# OUTPUTS.net
KiCad netlist of a schematic drawn in Altium Designer
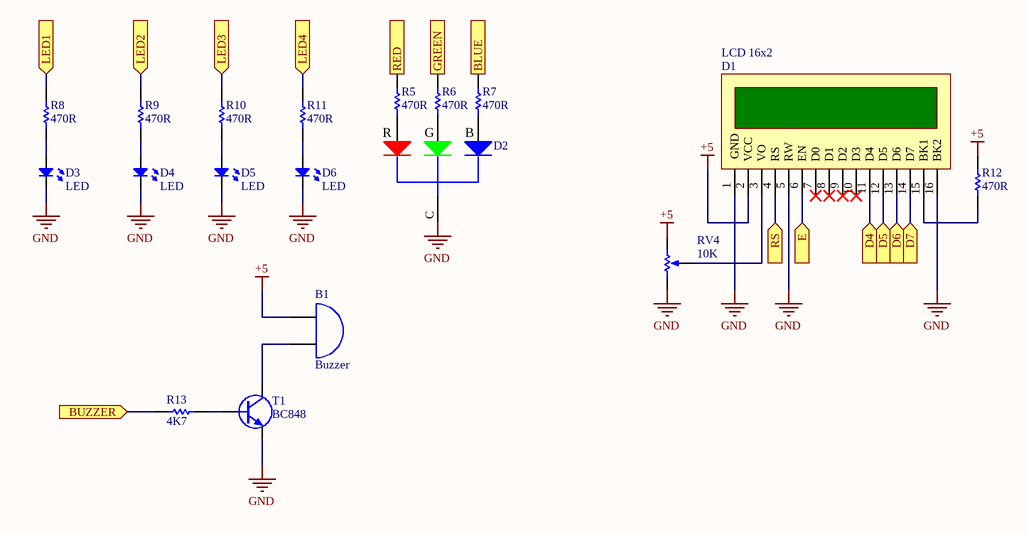
[diagram p0: OUTPUTS.SchDoc]

(export (version "E")
  (design (tool "Eeschema 10.0.6"))
  (components
    (comp (ref "B1")
      (value "Buzzer")
      (footprint "Buzzer")
      (description "Piezoeletric")
      (fields
        (field (name "MANUFACTURER") "Projects Unlimited")
        (field (name "MANUFACTURER PART NUMBER") "AT-1224-TWT-5V-2-R")
      )
      (libsource (lib "Adono_Library2") (part "Buzzer"))
    )
    (comp (ref "D1")
      (value "LCD 16x2")
      (footprint "LCD_16X2")
      (description "Liquid Crystal Display 16x2")
      (fields
        (field (name "MANUFACTURER") "Lumex")
        (field (name "MANUFACTURER PART NUMBER") "LCM-S01602DSR/A")
      )
      (libsource (lib "Adono_Library2") (part "LCD_16x2"))
    )
    (comp (ref "D2")
      (value "Led RGB")
      (footprint "RGB-5mm")
      (description "Led RGB 4 pin Cathode Commom")
      (libsource (lib "Adono_Library2") (part "RGB"))
    )
    (comp (ref "D3")
      (value "LED")
      (footprint "LED_GREEN")
      (description "Light Emissor Diode - 5mm")
      (fields
        (field (name "MANUFACTURER") "Kingbright")
        (field (name "MANUFACTURER PART NUMBER") "WP7113LGD")
      )
      (libsource (lib "Adono_Library2") (part "LED-GREEN"))
    )
    (comp (ref "D4")
      (value "LED")
      (footprint "LED_GREEN")
      (description "Light Emissor Diode - 5mm")
      (fields
        (field (name "MANUFACTURER") "Kingbright")
        (field (name "MANUFACTURER PART NUMBER") "WP7113LGD")
      )
      (libsource (lib "Adono_Library2") (part "LED-GREEN"))
    )
    (comp (ref "D5")
      (value "LED")
      (footprint "LED_GREEN")
      (description "Light Emissor Diode - 5mm")
      (fields
        (field (name "MANUFACTURER") "Kingbright")
        (field (name "MANUFACTURER PART NUMBER") "WP7113LGD")
      )
      (libsource (lib "Adono_Library2") (part "LED-GREEN"))
    )
    (comp (ref "D6")
      (value "LED")
      (footprint "LED_GREEN")
      (description "Light Emissor Diode - 5mm")
      (fields
        (field (name "MANUFACTURER") "Kingbright")
        (field (name "MANUFACTURER PART NUMBER") "WP7113LGD")
      )
      (libsource (lib "Adono_Library2") (part "LED-GREEN"))
    )
    (comp (ref "R5")
      (value "470R")
      (footprint "SMD Resistor")
      (description "SMD Resistor  MCU 0805")
      (libsource (lib "Aken") (part "SMD Resistor"))
    )
    (comp (ref "R6")
      (value "470R")
      (footprint "SMD Resistor")
      (description "SMD Resistor  MCU 0805")
      (libsource (lib "Aken") (part "SMD Resistor"))
    )
    (comp (ref "R7")
      (value "470R")
      (footprint "SMD Resistor")
      (description "SMD Resistor  MCU 0805")
      (libsource (lib "Aken") (part "SMD Resistor"))
    )
    (comp (ref "R8")
      (value "470R")
      (footprint "SMD Resistor")
      (description "SMD Resistor  MCU 0805")
      (libsource (lib "Aken") (part "SMD Resistor"))
    )
    (comp (ref "R9")
      (value "470R")
      (footprint "SMD Resistor")
      (description "SMD Resistor  MCU 0805")
      (libsource (lib "Aken") (part "SMD Resistor"))
    )
    (comp (ref "R10")
      (value "470R")
      (footprint "SMD Resistor")
      (description "SMD Resistor  MCU 0805")
      (libsource (lib "Aken") (part "SMD Resistor"))
    )
    (comp (ref "R11")
      (value "470R")
      (footprint "SMD Resistor")
      (description "SMD Resistor  MCU 0805")
      (libsource (lib "Aken") (part "SMD Resistor"))
    )
    (comp (ref "R12")
      (value "470R")
      (footprint "SMD Resistor")
      (description "SMD Resistor  MCU 0805")
      (libsource (lib "Aken") (part "SMD Resistor"))
    )
    (comp (ref "R13")
      (value "4K7")
      (footprint "SMD Resistor")
      (description "SMD Resistor  MCU 0805")
      (libsource (lib "SENAI-DEVPICKIT-V2.0") (part "SMD Resistor"))
    )
    (comp (ref "RV4")
      (value "10K")
      (footprint "Trimpot")
      (description "TRIMMER 10K OHM 0.5W TH")
      (fields
        (field (name "MANUFACTURER") "Murata")
        (field (name "MANUFACTURER PART NUMBER") "PV36W103C01B00")
      )
      (libsource (lib "Adono_Library2") (part "Trimpot"))
    )
    (comp (ref "T1")
      (value "BC848")
      (footprint "SOT-23")
      (description "NPN Epitaxial Silicon Transistor.")
      (fields
        (field (name "MANUFACTURER") "ON Semiconductor")
        (field (name "MANUFACTURER PART NUMBER") "BC848BLT3G")
      )
      (libsource (lib "Adono_Library") (part "BC848"))
    )
  )
  (nets
    (net (code "1") (name "+5") (class "Default")
      (node (ref "B1") (pin "1") (pinfunction "A_1") (pintype "passive"))
      (node (ref "D1") (pin "2") (pinfunction "VCC_2") (pintype "passive"))
      (node (ref "R12") (pin "2") (pinfunction "2_2") (pintype "passive"))
      (node (ref "RV4") (pin "3") (pinfunction "BOT_3") (pintype "passive"))
    )
    (net (code "2") (name "/BLUE") (class "Default")
      (node (ref "R7") (pin "2") (pinfunction "2_2") (pintype "passive"))
    )
    (net (code "3") (name "/BUZZER") (class "Default")
      (node (ref "R13") (pin "1") (pinfunction "1_1") (pintype "passive"))
    )
    (net (code "4") (name "/D4") (class "Default")
      (node (ref "D1") (pin "11") (pinfunction "D4_11") (pintype "passive"))
    )
    (net (code "5") (name "/D5") (class "Default")
      (node (ref "D1") (pin "12") (pinfunction "D5_12") (pintype "passive"))
    )
    (net (code "6") (name "/D6") (class "Default")
      (node (ref "D1") (pin "13") (pinfunction "D6_13") (pintype "passive"))
    )
    (net (code "7") (name "/D7") (class "Default")
      (node (ref "D1") (pin "14") (pinfunction "D7_14") (pintype "passive"))
    )
    (net (code "8") (name "/E") (class "Default")
      (node (ref "D1") (pin "6") (pinfunction "EN_6") (pintype "passive"))
    )
    (net (code "9") (name "/GREEN") (class "Default")
      (node (ref "R6") (pin "2") (pinfunction "2_2") (pintype "passive"))
    )
    (net (code "10") (name "/LED1") (class "Default")
      (node (ref "R8") (pin "2") (pinfunction "2_2") (pintype "passive"))
    )
    (net (code "11") (name "/LED2") (class "Default")
      (node (ref "R9") (pin "2") (pinfunction "2_2") (pintype "passive"))
    )
    (net (code "12") (name "/LED3") (class "Default")
      (node (ref "R10") (pin "2") (pinfunction "2_2") (pintype "passive"))
    )
    (net (code "13") (name "/LED4") (class "Default")
      (node (ref "R11") (pin "2") (pinfunction "2_2") (pintype "passive"))
    )
    (net (code "14") (name "/RED") (class "Default")
      (node (ref "R5") (pin "2") (pinfunction "2_2") (pintype "passive"))
    )
    (net (code "15") (name "/RS") (class "Default")
      (node (ref "D1") (pin "4") (pinfunction "RS_4") (pintype "passive"))
    )
    (net (code "16") (name "GND") (class "Default")
      (node (ref "D1") (pin "1") (pinfunction "GND_1") (pintype "passive"))
      (node (ref "D1") (pin "16") (pinfunction "BK2_16") (pintype "passive"))
      (node (ref "D1") (pin "5") (pinfunction "RW_5") (pintype "passive"))
      (node (ref "D2") (pin "C") (pinfunction "C_C") (pintype "passive"))
      (node (ref "D3") (pin "K") (pinfunction "K_K") (pintype "passive"))
      (node (ref "D4") (pin "K") (pinfunction "K_K") (pintype "passive"))
      (node (ref "D5") (pin "K") (pinfunction "K_K") (pintype "passive"))
      (node (ref "D6") (pin "K") (pinfunction "K_K") (pintype "passive"))
      (node (ref "RV4") (pin "1") (pinfunction "TOP_1") (pintype "passive"))
      (node (ref "T1") (pin "3") (pinfunction "E_3") (pintype "passive"))
    )
    (net (code "17") (name "Net-(B1-B)") (class "Default")
      (node (ref "B1") (pin "2") (pinfunction "B_2") (pintype "passive"))
      (node (ref "T1") (pin "1") (pinfunction "C_1") (pintype "passive"))
    )
    (net (code "18") (name "Net-(D1-BK1)") (class "Default")
      (node (ref "D1") (pin "15") (pinfunction "BK1_15") (pintype "passive"))
      (node (ref "R12") (pin "1") (pinfunction "1_1") (pintype "passive"))
    )
    (net (code "19") (name "Net-(D1-VO)") (class "Default")
      (node (ref "D1") (pin "3") (pinfunction "VO_3") (pintype "passive"))
      (node (ref "RV4") (pin "2") (pinfunction "TAP_2") (pintype "passive"))
    )
    (net (code "20") (name "Net-(D2-PadB)") (class "Default")
      (node (ref "D2") (pin "B") (pinfunction "B_B") (pintype "passive"))
      (node (ref "R7") (pin "1") (pinfunction "1_1") (pintype "passive"))
    )
    (net (code "21") (name "Net-(D2-PadG)") (class "Default")
      (node (ref "D2") (pin "G") (pinfunction "G_G") (pintype "passive"))
      (node (ref "R6") (pin "1") (pinfunction "1_1") (pintype "passive"))
    )
    (net (code "22") (name "Net-(D2-PadR)") (class "Default")
      (node (ref "D2") (pin "R") (pinfunction "R_R") (pintype "passive"))
      (node (ref "R5") (pin "1") (pinfunction "1_1") (pintype "passive"))
    )
    (net (code "23") (name "Net-(D3-PadA)") (class "Default")
      (node (ref "D3") (pin "A") (pinfunction "A_A") (pintype "passive"))
      (node (ref "R8") (pin "1") (pinfunction "1_1") (pintype "passive"))
    )
    (net (code "24") (name "Net-(D4-PadA)") (class "Default")
      (node (ref "D4") (pin "A") (pinfunction "A_A") (pintype "passive"))
      (node (ref "R9") (pin "1") (pinfunction "1_1") (pintype "passive"))
    )
    (net (code "25") (name "Net-(D5-PadA)") (class "Default")
      (node (ref "D5") (pin "A") (pinfunction "A_A") (pintype "passive"))
      (node (ref "R10") (pin "1") (pinfunction "1_1") (pintype "passive"))
    )
    (net (code "26") (name "Net-(D6-PadA)") (class "Default")
      (node (ref "D6") (pin "A") (pinfunction "A_A") (pintype "passive"))
      (node (ref "R11") (pin "1") (pinfunction "1_1") (pintype "passive"))
    )
    (net (code "27") (name "Net-(T1-B)") (class "Default")
      (node (ref "R13") (pin "2") (pinfunction "2_2") (pintype "passive"))
      (node (ref "T1") (pin "2") (pinfunction "B_2") (pintype "passive"))
    )
    (net (code "28") (name "unconnected-(D1-D0-Pad7)") (class "Default")
      (node (ref "D1") (pin "7") (pinfunction "D0_7") (pintype "passive+no_connect"))
    )
    (net (code "29") (name "unconnected-(D1-D1-Pad8)") (class "Default")
      (node (ref "D1") (pin "8") (pinfunction "D1_8") (pintype "passive+no_connect"))
    )
    (net (code "30") (name "unconnected-(D1-D2-Pad9)") (class "Default")
      (node (ref "D1") (pin "9") (pinfunction "D2_9") (pintype "passive+no_connect"))
    )
    (net (code "31") (name "unconnected-(D1-D3-Pad10)") (class "Default")
      (node (ref "D1") (pin "10") (pinfunction "D3_10") (pintype "passive+no_connect"))
    )
  )
)
